# Wheel_Encoder_Adapter_Schmitt_7414.net
KiCad netlist of a schematic drawn in EAGLE
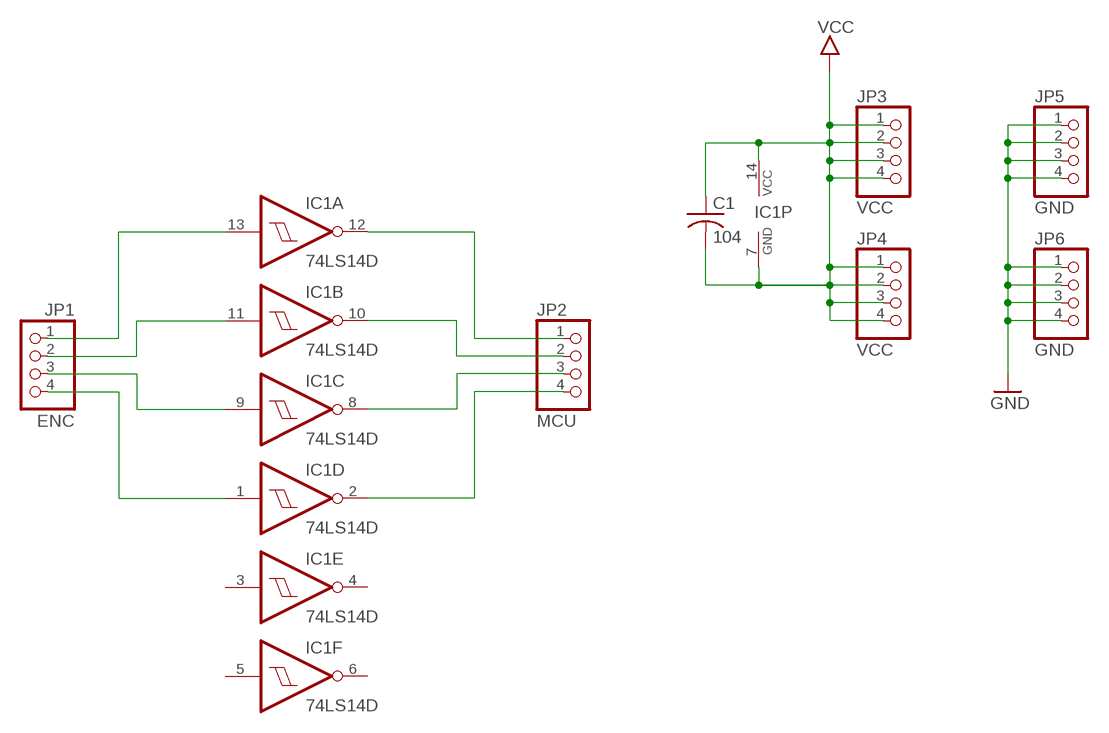
[diagram p0: schematic, sheet 1]

(export (version "E")
  (design (tool "Eeschema 10.0.6"))
  (components
    (comp (ref "C1")
      (value "104")
      (footprint "eagle-import:C0603")
      (libsource (lib "eagle-import") (part "C-USC0603"))
    )
    (comp (ref "IC1")
      (value "74LS14D")
      (footprint "eagle-import:SO14")
      (libsource (lib "eagle-import") (part "7414DLS"))
    )
    (comp (ref "JP1")
      (value "ENC")
      (footprint "eagle-import:1X04-S")
      (libsource (lib "eagle-import") (part "PINHD-1X04_2.54-S"))
    )
    (comp (ref "JP2")
      (value "MCU")
      (footprint "eagle-import:1X04-S")
      (libsource (lib "eagle-import") (part "PINHD-1X04_2.54-S"))
    )
    (comp (ref "JP3")
      (value "VCC")
      (footprint "eagle-import:1X04-S")
      (libsource (lib "eagle-import") (part "PINHD-1X04_2.54-S"))
    )
    (comp (ref "JP4")
      (value "VCC")
      (footprint "eagle-import:1X04-S")
      (libsource (lib "eagle-import") (part "PINHD-1X04_2.54-S"))
    )
    (comp (ref "JP5")
      (value "GND")
      (footprint "eagle-import:1X04-S")
      (libsource (lib "eagle-import") (part "PINHD-1X04_2.54-S"))
    )
    (comp (ref "JP6")
      (value "GND")
      (footprint "eagle-import:1X04-S")
      (libsource (lib "eagle-import") (part "PINHD-1X04_2.54-S"))
    )
  )
  (nets
    (net (code "1") (name "GND") (class "Default")
      (node (ref "JP5") (pin "1") (pinfunction "1_1") (pintype "passive"))
      (node (ref "JP5") (pin "2") (pinfunction "2_2") (pintype "passive"))
      (node (ref "JP5") (pin "3") (pinfunction "3_3") (pintype "passive"))
      (node (ref "JP5") (pin "4") (pinfunction "4_4") (pintype "passive"))
      (node (ref "JP6") (pin "1") (pinfunction "1_1") (pintype "passive"))
      (node (ref "JP6") (pin "2") (pinfunction "2_2") (pintype "passive"))
      (node (ref "JP6") (pin "3") (pinfunction "3_3") (pintype "passive"))
      (node (ref "JP6") (pin "4") (pinfunction "4_4") (pintype "passive"))
    )
    (net (code "2") (name "Net-(IC1A-I)") (class "Default")
      (node (ref "IC1") (pin "13") (pinfunction "I_13") (pintype "input"))
      (node (ref "JP1") (pin "1") (pinfunction "1_1") (pintype "passive"))
    )
    (net (code "3") (name "Net-(IC1A-O)") (class "Default")
      (node (ref "IC1") (pin "12") (pinfunction "O_12") (pintype "output"))
      (node (ref "JP2") (pin "1") (pinfunction "1_1") (pintype "passive"))
    )
    (net (code "4") (name "Net-(IC1B-I)") (class "Default")
      (node (ref "IC1") (pin "11") (pinfunction "I_11") (pintype "input"))
      (node (ref "JP1") (pin "2") (pinfunction "2_2") (pintype "passive"))
    )
    (net (code "5") (name "Net-(IC1B-O)") (class "Default")
      (node (ref "IC1") (pin "10") (pinfunction "O_10") (pintype "output"))
      (node (ref "JP2") (pin "2") (pinfunction "2_2") (pintype "passive"))
    )
    (net (code "6") (name "Net-(IC1C-I)") (class "Default")
      (node (ref "IC1") (pin "9") (pinfunction "I_9") (pintype "input"))
      (node (ref "JP1") (pin "3") (pinfunction "3_3") (pintype "passive"))
    )
    (net (code "7") (name "Net-(IC1C-O)") (class "Default")
      (node (ref "IC1") (pin "8") (pinfunction "O_8") (pintype "output"))
      (node (ref "JP2") (pin "3") (pinfunction "3_3") (pintype "passive"))
    )
    (net (code "8") (name "Net-(IC1D-I)") (class "Default")
      (node (ref "IC1") (pin "1") (pinfunction "I_1") (pintype "input"))
      (node (ref "JP1") (pin "4") (pinfunction "4_4") (pintype "passive"))
    )
    (net (code "9") (name "Net-(IC1D-O)") (class "Default")
      (node (ref "IC1") (pin "2") (pinfunction "O_2") (pintype "output"))
      (node (ref "JP2") (pin "4") (pinfunction "4_4") (pintype "passive"))
    )
    (net (code "10") (name "VCC") (class "Default")
      (node (ref "C1") (pin "1") (pinfunction "1_1") (pintype "passive"))
      (node (ref "C1") (pin "2") (pinfunction "2_2") (pintype "passive"))
      (node (ref "IC1") (pin "14") (pinfunction "VCC_14") (pintype "power_in"))
      (node (ref "IC1") (pin "7") (pinfunction "GND_7") (pintype "power_in"))
      (node (ref "JP3") (pin "1") (pinfunction "1_1") (pintype "passive"))
      (node (ref "JP3") (pin "2") (pinfunction "2_2") (pintype "passive"))
      (node (ref "JP3") (pin "3") (pinfunction "3_3") (pintype "passive"))
      (node (ref "JP3") (pin "4") (pinfunction "4_4") (pintype "passive"))
      (node (ref "JP4") (pin "1") (pinfunction "1_1") (pintype "passive"))
      (node (ref "JP4") (pin "2") (pinfunction "2_2") (pintype "passive"))
      (node (ref "JP4") (pin "3") (pinfunction "3_3") (pintype "passive"))
      (node (ref "JP4") (pin "4") (pinfunction "4_4") (pintype "passive"))
    )
    (net (code "11") (name "unconnected-(IC1E-I-Pad3)") (class "Default")
      (node (ref "IC1") (pin "3") (pinfunction "I_3") (pintype "input"))
    )
    (net (code "12") (name "unconnected-(IC1E-O-Pad4)") (class "Default")
      (node (ref "IC1") (pin "4") (pinfunction "O_4") (pintype "output"))
    )
    (net (code "13") (name "unconnected-(IC1F-I-Pad5)") (class "Default")
      (node (ref "IC1") (pin "5") (pinfunction "I_5") (pintype "input"))
    )
    (net (code "14") (name "unconnected-(IC1F-O-Pad6)") (class "Default")
      (node (ref "IC1") (pin "6") (pinfunction "O_6") (pintype "output"))
    )
  )
)
